# Sheet_v1.net
KiCad netlist of a schematic drawn in Altium Designer
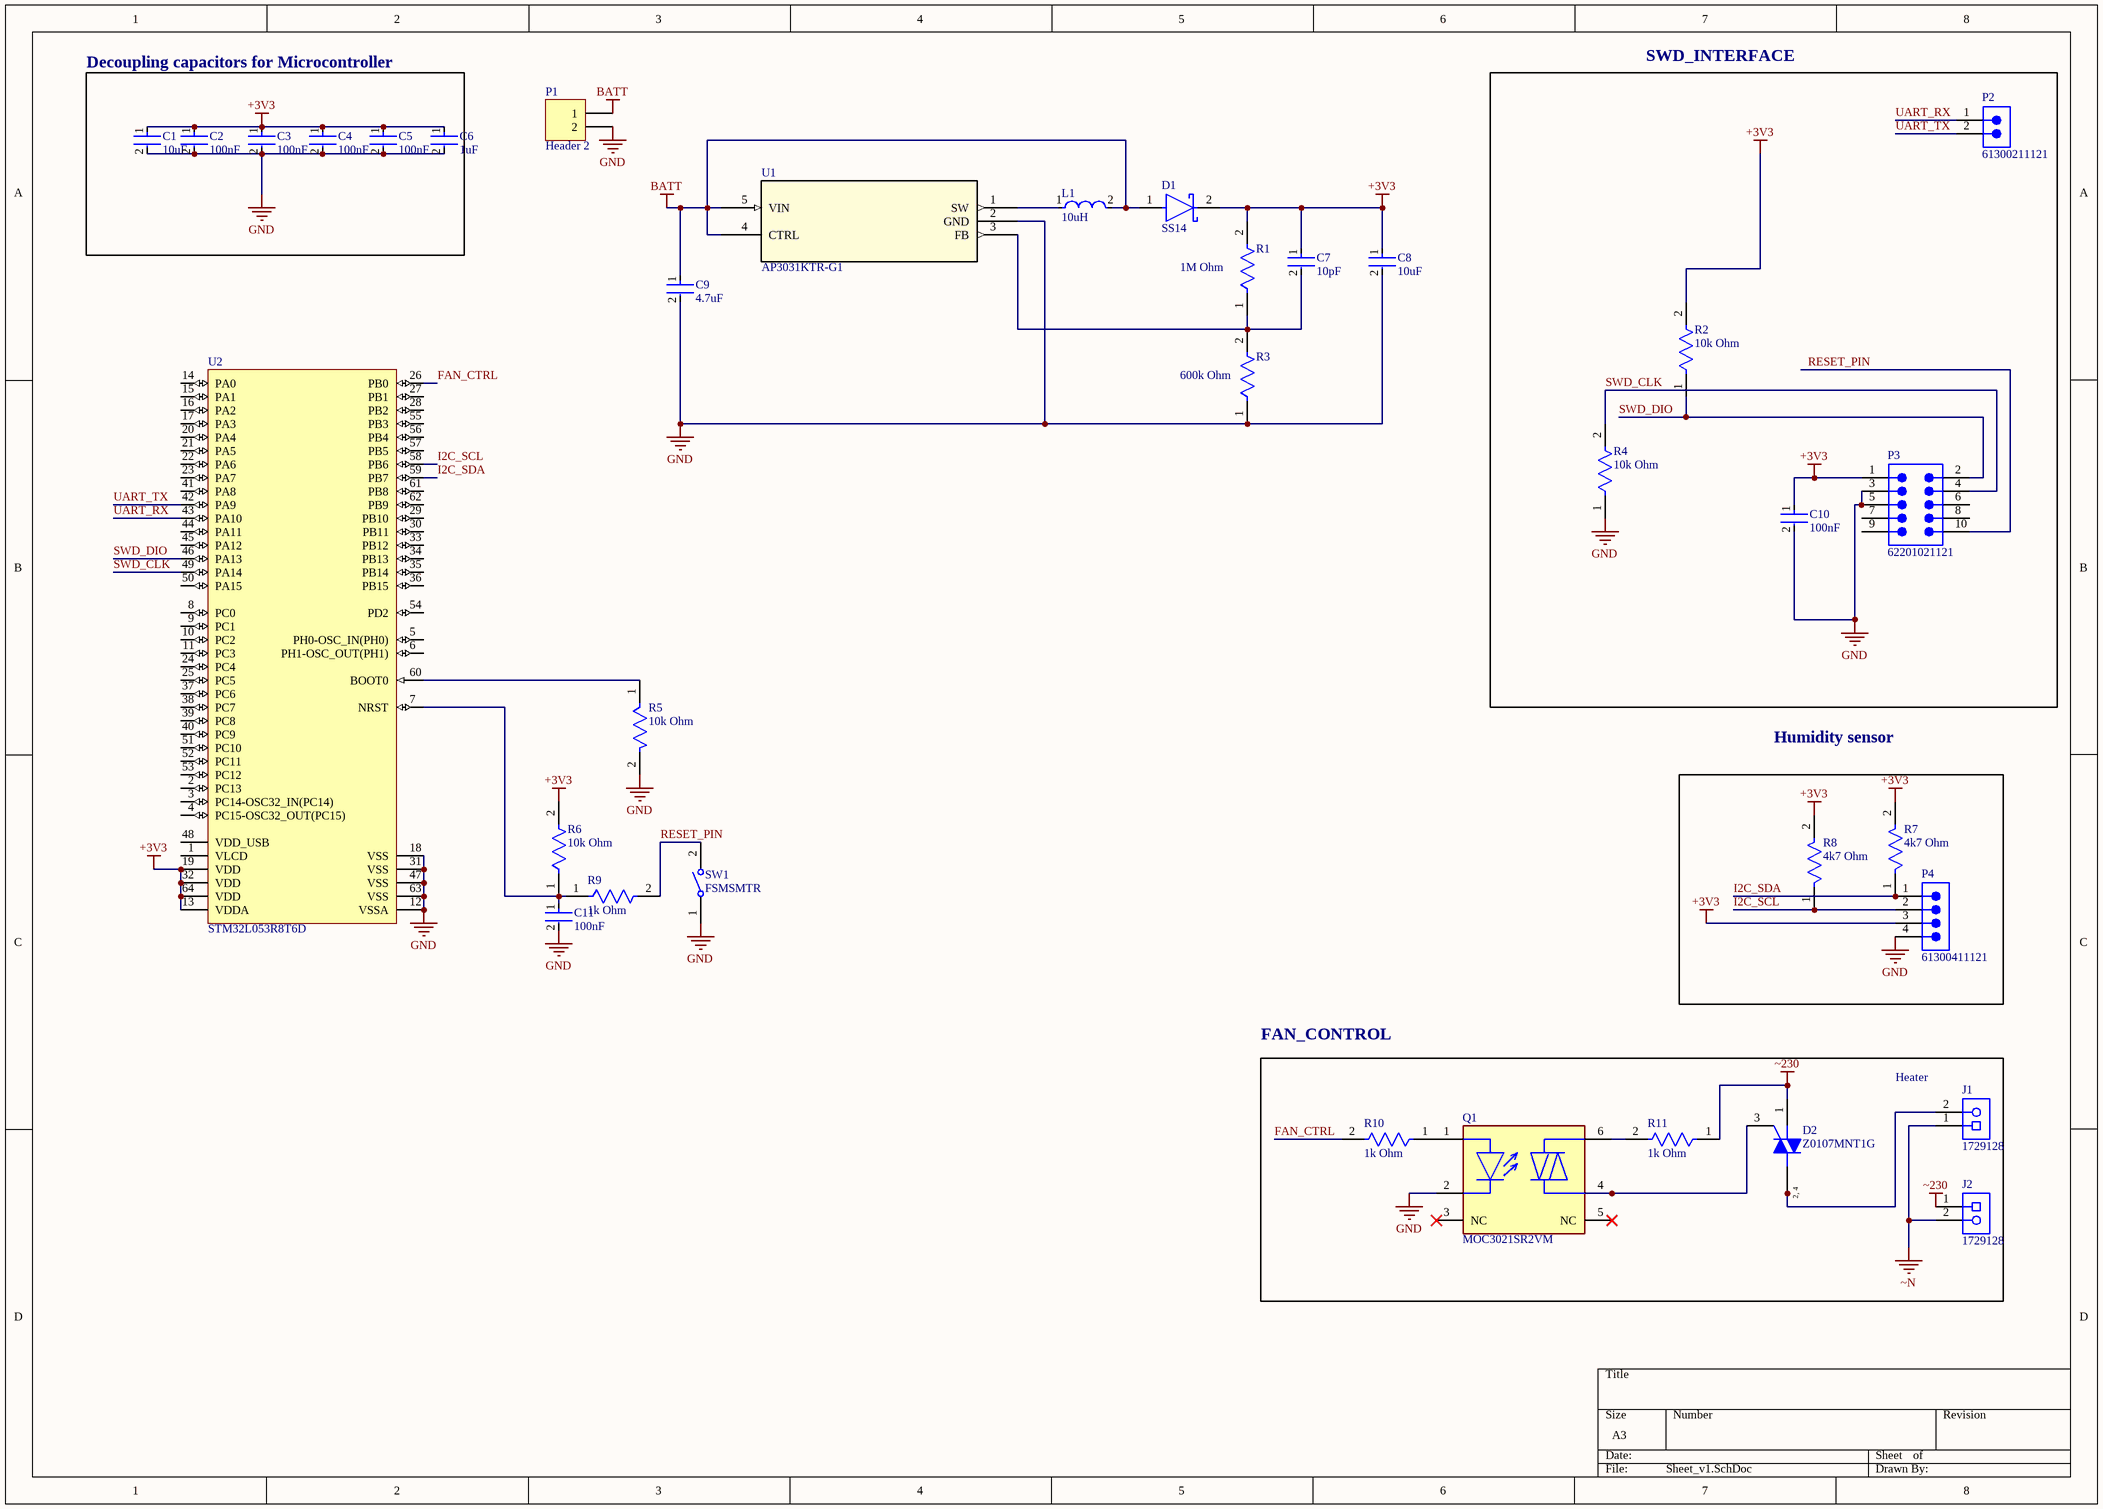
[diagram p0: Sheet_v1.SchDoc]

(export (version "E")
  (design (tool "Eeschema 10.0.6"))
  (components
    (comp (ref "C1")
      (value "10uF")
      (footprint "FP-CC0805-0_85-MFG")
      (description "CAP CER 0.1UF 50V X7R 0805")
      (fields (field (name "TOLERANCE") "0.1") (field (name "MANUFACTURER PART NUMBER") "CC0805KRX7R9BB104"))
      (libsource (lib "Altium Content Vault") (part "11868f565c42a9108669ba33697ecf6"))
    )
    (comp (ref "C2")
      (value "100nF")
      (footprint "FP-CC0805-0_85-MFG")
      (description "CAP CER 0.1UF 50V X7R 0805")
      (fields (field (name "TOLERANCE") "0.1") (field (name "MANUFACTURER PART NUMBER") "CC0805KRX7R9BB104"))
      (libsource (lib "Altium Content Vault") (part "11868f565c42a9108669ba33697ecf6"))
    )
    (comp (ref "C3")
      (value "100nF")
      (footprint "FP-CC0805-0_85-MFG")
      (description "CAP CER 0.1UF 50V X7R 0805")
      (fields (field (name "TOLERANCE") "0.1") (field (name "MANUFACTURER PART NUMBER") "CC0805KRX7R9BB104"))
      (libsource (lib "Altium Content Vault") (part "11868f565c42a9108669ba33697ecf6"))
    )
    (comp (ref "C4")
      (value "100nF")
      (footprint "FP-CC0805-0_85-MFG")
      (description "CAP CER 0.1UF 50V X7R 0805")
      (fields (field (name "TOLERANCE") "0.1") (field (name "MANUFACTURER PART NUMBER") "CC0805KRX7R9BB104"))
      (libsource (lib "Altium Content Vault") (part "11868f565c42a9108669ba33697ecf6"))
    )
    (comp (ref "C5")
      (value "100nF")
      (footprint "FP-CC0805-0_85-MFG")
      (description "CAP CER 0.1UF 50V X7R 0805")
      (fields (field (name "TOLERANCE") "0.1") (field (name "MANUFACTURER PART NUMBER") "CC0805KRX7R9BB104"))
      (libsource (lib "Altium Content Vault") (part "11868f565c42a9108669ba33697ecf6"))
    )
    (comp (ref "C6")
      (value "1uF")
      (footprint "FP-CC0805-0_85-MFG")
      (description "CAP CER 0.1UF 50V X7R 0805")
      (fields (field (name "TOLERANCE") "0.1") (field (name "MANUFACTURER PART NUMBER") "CC0805KRX7R9BB104"))
      (libsource (lib "Altium Content Vault") (part "11868f565c42a9108669ba33697ecf6"))
    )
    (comp (ref "C7")
      (value "10pF")
      (footprint "FP-CC0805-0_85-MFG")
      (description "CAP CER 0.1UF 50V X7R 0805")
      (fields (field (name "TOLERANCE") "0.1") (field (name "MANUFACTURER PART NUMBER") "CC0805KRX7R9BB104"))
      (libsource (lib "Altium Content Vault") (part "11868f565c42a9108669ba33697ecf6"))
    )
    (comp (ref "C8")
      (value "10uF")
      (footprint "FP-CC0805-0_85-MFG")
      (description "CAP CER 0.1UF 50V X7R 0805")
      (fields (field (name "TOLERANCE") "0.1") (field (name "MANUFACTURER PART NUMBER") "CC0805KRX7R9BB104"))
      (libsource (lib "Altium Content Vault") (part "11868f565c42a9108669ba33697ecf6"))
    )
    (comp (ref "C9")
      (value "4.7uF")
      (footprint "FP-CC0805-0_85-MFG")
      (description "CAP CER 0.1UF 50V X7R 0805")
      (fields (field (name "TOLERANCE") "0.1") (field (name "MANUFACTURER PART NUMBER") "CC0805KRX7R9BB104"))
      (libsource (lib "Altium Content Vault") (part "11868f565c42a9108669ba33697ecf6"))
    )
    (comp (ref "C10")
      (value "100nF")
      (footprint "FP-CC0805-0_85-MFG")
      (description "CAP CER 0.1UF 50V X7R 0805")
      (fields (field (name "TOLERANCE") "0.1") (field (name "MANUFACTURER PART NUMBER") "CC0805KRX7R9BB104"))
      (libsource (lib "Altium Content Vault") (part "11868f565c42a9108669ba33697ecf6"))
    )
    (comp (ref "C11")
      (value "100nF")
      (footprint "FP-CC0805-0_85-MFG")
      (description "CAP CER 0.1UF 50V X7R 0805")
      (fields (field (name "TOLERANCE") "0.1") (field (name "MANUFACTURER PART NUMBER") "CC0805KRX7R9BB104"))
      (libsource (lib "Altium Content Vault") (part "11868f565c42a9108669ba33697ecf6"))
    )
    (comp (ref "D1")
      (value "SS14")
      (footprint "FP-403AE-MFG")
      (description "DIODE SCHOTTKY 40V 1A SMA")
      (fields
        (field (name "MANUFACTURER") "ON Semiconductor")
        (field (name "OCTOPART") "https://octopart.com/ss14-on+semiconductor-29205033")
      )
      (libsource (lib "Altium Content Vault") (part "360ad2f4ac25a952324d13796385471"))
    )
    (comp (ref "D2")
      (value "Z0107MNT1G")
      (footprint "ONSC-SOT-223-4-318E-04_V")
      (fields (field (name "MANUFACTURER") "On Semiconductor"))
      (libsource (lib "Altium Content Vault") (part "ONSC-TRIAC-MT1MT2GMT2-4"))
    )
    (comp (ref "J1")
      (value "1729128")
      (footprint "PHOE-1729128-2_V")
      (description "PCB Terminal Block, 13.5 A, 400 V, 2-Pin THD, RoHS, Bulk")
      (fields (field (name "MANUFACTURER") "Phoenix Contact"))
      (libsource (lib "") (part "CN-2P-F-R2_1"))
    )
    (comp (ref "J2")
      (value "1729128")
      (footprint "PHOE-1729128-2_V")
      (description "PCB Terminal Block, 13.5 A, 400 V, 2-Pin THD, RoHS, Bulk")
      (fields (field (name "MANUFACTURER") "Phoenix Contact"))
      (libsource (lib "Altium Content Vault") (part "CN-2P-F-R2"))
    )
    (comp (ref "L1")
      (value "10uH")
      (footprint "FP-LQH43CN_03-MFG")
      (description "Wire Wound Ferrite Inductor for General Circuits 470μH ±10% 11.8Ω 80mA 1812")
      (fields (field (name "TOLERANCE") "10%"))
      (libsource (lib "Altium Content Vault") (part "725321dda6339637d4d059423bc1c3c"))
    )
    (comp (ref "P1")
      (value "Header 2")
      (footprint "HDR1X2")
      (description "Header, 2-Pin")
      (fields (field (name "PUBLISHER") "Altium Limited"))
      (libsource (lib "Miscellaneous Connectors") (part "Header 2"))
    )
    (comp (ref "P2")
      (value "61300211121")
      (footprint "61300211121")
      (libsource (lib "Altium Content Vault") (part "Header_Male_1R_02P"))
    )
    (comp (ref "P3")
      (value "62201021121")
      (footprint "62201021121")
      (libsource (lib "Altium Content Vault") (part "Header_Male_2R_10P"))
    )
    (comp (ref "P4")
      (value "61300411121")
      (footprint "61300411121")
      (libsource (lib "Altium Content Vault") (part "Header_Male_1R_04P"))
    )
    (comp (ref "Q1")
      (value "MOC3021SR2VM")
      (footprint "FP-646BY-MFG")
      (description "MOC3021SR2VM Triac Driver Output Optocoupler, 6-Pin DIP 400V Random Phase")
      (libsource (lib "Altium Content Vault") (part "315d33d7a3de83856d3bd334bf87c2f"))
    )
    (comp (ref "R1")
      (value "1M Ohm")
      (footprint "FP-RMCF0805-MFG")
      (description "RES 0 OHM JUMPER 1/8W 0805")
      (libsource (lib "Altium Content Vault") (part "1029c3af85768c4190bb7ad29bc67b5"))
    )
    (comp (ref "R2")
      (value "10k Ohm")
      (footprint "FP-RMCF0805-MFG")
      (description "RES 0 OHM JUMPER 1/8W 0805")
      (libsource (lib "Altium Content Vault") (part "1029c3af85768c4190bb7ad29bc67b5"))
    )
    (comp (ref "R3")
      (value "600k Ohm")
      (footprint "FP-RMCF0805-MFG")
      (description "RES 0 OHM JUMPER 1/8W 0805")
      (libsource (lib "Altium Content Vault") (part "1029c3af85768c4190bb7ad29bc67b5"))
    )
    (comp (ref "R4")
      (value "10k Ohm")
      (footprint "FP-RMCF0805-MFG")
      (description "RES 0 OHM JUMPER 1/8W 0805")
      (libsource (lib "Altium Content Vault") (part "1029c3af85768c4190bb7ad29bc67b5"))
    )
    (comp (ref "R5")
      (value "10k Ohm")
      (footprint "FP-RMCF0805-MFG")
      (description "RES 0 OHM JUMPER 1/8W 0805")
      (libsource (lib "Altium Content Vault") (part "1029c3af85768c4190bb7ad29bc67b5"))
    )
    (comp (ref "R6")
      (value "10k Ohm")
      (footprint "FP-RMCF0805-MFG")
      (description "RES 0 OHM JUMPER 1/8W 0805")
      (libsource (lib "Altium Content Vault") (part "1029c3af85768c4190bb7ad29bc67b5"))
    )
    (comp (ref "R7")
      (value "4k7 Ohm")
      (footprint "FP-RMCF0805-MFG")
      (description "RES 0 OHM JUMPER 1/8W 0805")
      (libsource (lib "Altium Content Vault") (part "1029c3af85768c4190bb7ad29bc67b5"))
    )
    (comp (ref "R8")
      (value "4k7 Ohm")
      (footprint "FP-RMCF0805-MFG")
      (description "RES 0 OHM JUMPER 1/8W 0805")
      (libsource (lib "Altium Content Vault") (part "1029c3af85768c4190bb7ad29bc67b5"))
    )
    (comp (ref "R9")
      (value "1k Ohm")
      (footprint "FP-RMCF0805-MFG")
      (description "RES 0 OHM JUMPER 1/8W 0805")
      (libsource (lib "Altium Content Vault") (part "1029c3af85768c4190bb7ad29bc67b5"))
    )
    (comp (ref "R10")
      (value "1k Ohm")
      (footprint "FP-RMCF0805-MFG")
      (description "RES 0 OHM JUMPER 1/8W 0805")
      (libsource (lib "Altium Content Vault") (part "1029c3af85768c4190bb7ad29bc67b5"))
    )
    (comp (ref "R11")
      (value "1k Ohm")
      (footprint "FP-RMCF0805-MFG")
      (description "RES 0 OHM JUMPER 1/8W 0805")
      (libsource (lib "Altium Content Vault") (part "1029c3af85768c4190bb7ad29bc67b5"))
    )
    (comp (ref "SW1")
      (value "FSMSMTR")
      (footprint "TECO-FSMSMTR_V")
      (description "FSMSM Push Button Switch, 50 mA, -35 to 85 degC, 2-Pin SMD, RoHS, Tape and Reel")
      (fields (field (name "MANUFACTURER") "TE Connectivity"))
      (libsource (lib "Altium Content Vault") (part "SW-SPST-2_C"))
    )
    (comp (ref "U1")
      (value "AP3031KTR-G1")
      (footprint "SOT23-6_DIO")
      (description "No Description Available")
      (libsource (lib "AP3031KTR-G1") (part "AP3031KTR-G1"))
    )
    (comp (ref "U2")
      (value "STM32L053R8T6D")
      (footprint "STM-LQFP64_L")
      (libsource (lib "Altium Content Vault") (part "MC-ARM-STM32L053-LQFP64"))
    )
  )
  (nets
    (net (code "1") (name "+3V3") (class "Default")
      (node (ref "C1") (pin "1") (pinfunction "1_1") (pintype "passive"))
      (node (ref "C10") (pin "1") (pinfunction "1_1") (pintype "passive"))
      (node (ref "C2") (pin "1") (pinfunction "1_1") (pintype "passive"))
      (node (ref "C3") (pin "1") (pinfunction "1_1") (pintype "passive"))
      (node (ref "C4") (pin "1") (pinfunction "1_1") (pintype "passive"))
      (node (ref "C5") (pin "1") (pinfunction "1_1") (pintype "passive"))
      (node (ref "C6") (pin "1") (pinfunction "1_1") (pintype "passive"))
      (node (ref "C7") (pin "1") (pinfunction "1_1") (pintype "passive"))
      (node (ref "C8") (pin "1") (pinfunction "1_1") (pintype "passive"))
      (node (ref "D1") (pin "2") (pinfunction "C_2") (pintype "passive"))
      (node (ref "P3") (pin "1") (pinfunction "1_1") (pintype "passive"))
      (node (ref "P4") (pin "3") (pinfunction "3_3") (pintype "passive"))
      (node (ref "R1") (pin "2") (pinfunction "2_2") (pintype "passive"))
      (node (ref "R2") (pin "2") (pinfunction "2_2") (pintype "passive"))
      (node (ref "R6") (pin "2") (pinfunction "2_2") (pintype "passive"))
      (node (ref "R7") (pin "2") (pinfunction "2_2") (pintype "passive"))
      (node (ref "R8") (pin "2") (pinfunction "2_2") (pintype "passive"))
      (node (ref "U2") (pin "13") (pinfunction "VDDA_13") (pintype "power_in"))
      (node (ref "U2") (pin "19") (pinfunction "VDD_19") (pintype "power_in"))
      (node (ref "U2") (pin "32") (pinfunction "VDD_32") (pintype "power_in"))
      (node (ref "U2") (pin "64") (pinfunction "VDD_64") (pintype "power_in"))
    )
    (net (code "2") (name "/FAN_CTRL") (class "Default")
      (node (ref "R10") (pin "2") (pinfunction "2_2") (pintype "passive"))
      (node (ref "U2") (pin "26") (pinfunction "PB0_26") (pintype "bidirectional"))
    )
    (net (code "3") (name "/I2C_SCL") (class "Default")
      (node (ref "P4") (pin "2") (pinfunction "2_2") (pintype "passive"))
      (node (ref "R8") (pin "1") (pinfunction "1_1") (pintype "passive"))
      (node (ref "U2") (pin "58") (pinfunction "PB6_58") (pintype "bidirectional"))
    )
    (net (code "4") (name "/I2C_SDA") (class "Default")
      (node (ref "P4") (pin "1") (pinfunction "1_1") (pintype "passive"))
      (node (ref "R7") (pin "1") (pinfunction "1_1") (pintype "passive"))
      (node (ref "U2") (pin "59") (pinfunction "PB7_59") (pintype "bidirectional"))
    )
    (net (code "5") (name "/RESET_PIN") (class "Default")
      (node (ref "P3") (pin "10") (pinfunction "10_10") (pintype "passive"))
      (node (ref "R9") (pin "2") (pinfunction "2_2") (pintype "passive"))
      (node (ref "SW1") (pin "2") (pinfunction "2_2") (pintype "passive"))
    )
    (net (code "6") (name "/SWD_CLK") (class "Default")
      (node (ref "P3") (pin "4") (pinfunction "4_4") (pintype "passive"))
      (node (ref "R4") (pin "2") (pinfunction "2_2") (pintype "passive"))
      (node (ref "U2") (pin "49") (pinfunction "PA14_49") (pintype "bidirectional"))
    )
    (net (code "7") (name "/SWD_DIO") (class "Default")
      (node (ref "P3") (pin "2") (pinfunction "2_2") (pintype "passive"))
      (node (ref "R2") (pin "1") (pinfunction "1_1") (pintype "passive"))
      (node (ref "U2") (pin "46") (pinfunction "PA13_46") (pintype "bidirectional"))
    )
    (net (code "8") (name "/UART_RX") (class "Default")
      (node (ref "P2") (pin "1") (pinfunction "1_1") (pintype "passive"))
      (node (ref "U2") (pin "43") (pinfunction "PA10_43") (pintype "bidirectional"))
    )
    (net (code "9") (name "/UART_TX") (class "Default")
      (node (ref "P2") (pin "2") (pinfunction "2_2") (pintype "passive"))
      (node (ref "U2") (pin "42") (pinfunction "PA9_42") (pintype "bidirectional"))
    )
    (net (code "10") (name "BATT") (class "Default")
      (node (ref "C9") (pin "1") (pinfunction "1_1") (pintype "passive"))
      (node (ref "D1") (pin "1") (pinfunction "A_1") (pintype "passive"))
      (node (ref "L1") (pin "2") (pinfunction "2_2") (pintype "passive"))
      (node (ref "P1") (pin "1") (pinfunction "1_1") (pintype "passive"))
      (node (ref "U1") (pin "4") (pinfunction "CTRL_4") (pintype "passive"))
      (node (ref "U1") (pin "5") (pinfunction "VIN_5") (pintype "input"))
    )
    (net (code "11") (name "GND") (class "Default")
      (node (ref "C1") (pin "2") (pinfunction "2_2") (pintype "passive"))
      (node (ref "C10") (pin "2") (pinfunction "2_2") (pintype "passive"))
      (node (ref "C11") (pin "2") (pinfunction "2_2") (pintype "passive"))
      (node (ref "C2") (pin "2") (pinfunction "2_2") (pintype "passive"))
      (node (ref "C3") (pin "2") (pinfunction "2_2") (pintype "passive"))
      (node (ref "C4") (pin "2") (pinfunction "2_2") (pintype "passive"))
      (node (ref "C5") (pin "2") (pinfunction "2_2") (pintype "passive"))
      (node (ref "C6") (pin "2") (pinfunction "2_2") (pintype "passive"))
      (node (ref "C8") (pin "2") (pinfunction "2_2") (pintype "passive"))
      (node (ref "C9") (pin "2") (pinfunction "2_2") (pintype "passive"))
      (node (ref "P1") (pin "2") (pinfunction "2_2") (pintype "passive"))
      (node (ref "P3") (pin "3") (pinfunction "3_3") (pintype "passive"))
      (node (ref "P3") (pin "5") (pinfunction "5_5") (pintype "passive"))
      (node (ref "P4") (pin "4") (pinfunction "4_4") (pintype "passive"))
      (node (ref "Q1") (pin "2") (pinfunction "C_2") (pintype "passive"))
      (node (ref "R3") (pin "1") (pinfunction "1_1") (pintype "passive"))
      (node (ref "R4") (pin "1") (pinfunction "1_1") (pintype "passive"))
      (node (ref "R5") (pin "2") (pinfunction "2_2") (pintype "passive"))
      (node (ref "SW1") (pin "1") (pinfunction "1_1") (pintype "passive"))
      (node (ref "U1") (pin "2") (pinfunction "GND_2") (pintype "power_in"))
      (node (ref "U2") (pin "12") (pinfunction "VSSA_12") (pintype "power_in"))
      (node (ref "U2") (pin "18") (pinfunction "VSS_18") (pintype "power_in"))
      (node (ref "U2") (pin "31") (pinfunction "VSS_31") (pintype "power_in"))
      (node (ref "U2") (pin "47") (pinfunction "VSS_47") (pintype "power_in"))
      (node (ref "U2") (pin "63") (pinfunction "VSS_63") (pintype "power_in"))
    )
    (net (code "12") (name "Net-(D2-G)") (class "Default")
      (node (ref "D2") (pin "3") (pinfunction "G_3") (pintype "passive"))
      (node (ref "Q1") (pin "4") (pinfunction "1_MAIN_TERM_4") (pintype "passive"))
    )
    (net (code "13") (name "Net-(D2-MT2-Pad2)") (class "Default")
      (node (ref "D2") (pin "2") (pinfunction "MT2_2") (pintype "passive"))
      (node (ref "D2") (pin "4") (pinfunction "MT2_4") (pintype "passive"))
      (node (ref "J1") (pin "2") (pinfunction "2_2") (pintype "passive"))
    )
    (net (code "14") (name "Net-(Q1-2_MAIN_TERM)") (class "Default")
      (node (ref "Q1") (pin "6") (pinfunction "2_MAIN_TERM_6") (pintype "passive"))
      (node (ref "R11") (pin "2") (pinfunction "2_2") (pintype "passive"))
    )
    (net (code "15") (name "Net-(Q1-A)") (class "Default")
      (node (ref "Q1") (pin "1") (pinfunction "A_1") (pintype "passive"))
      (node (ref "R10") (pin "1") (pinfunction "1_1") (pintype "passive"))
    )
    (net (code "16") (name "Net-(U1-FB)") (class "Default")
      (node (ref "C7") (pin "2") (pinfunction "2_2") (pintype "passive"))
      (node (ref "R1") (pin "1") (pinfunction "1_1") (pintype "passive"))
      (node (ref "R3") (pin "2") (pinfunction "2_2") (pintype "passive"))
      (node (ref "U1") (pin "3") (pinfunction "FB_3") (pintype "output"))
    )
    (net (code "17") (name "Net-(U1-SW)") (class "Default")
      (node (ref "L1") (pin "1") (pinfunction "1_1") (pintype "passive"))
      (node (ref "U1") (pin "1") (pinfunction "SW_1") (pintype "output"))
    )
    (net (code "18") (name "Net-(U2-BOOT0)") (class "Default")
      (node (ref "R5") (pin "1") (pinfunction "1_1") (pintype "passive"))
      (node (ref "U2") (pin "60") (pinfunction "BOOT0_60") (pintype "input"))
    )
    (net (code "19") (name "Net-(U2-NRST)") (class "Default")
      (node (ref "C11") (pin "1") (pinfunction "1_1") (pintype "passive"))
      (node (ref "R6") (pin "1") (pinfunction "1_1") (pintype "passive"))
      (node (ref "R9") (pin "1") (pinfunction "1_1") (pintype "passive"))
      (node (ref "U2") (pin "7") (pinfunction "NRST_7") (pintype "bidirectional"))
    )
    (net (code "20") (name "unconnected-(P3-Pad6)") (class "Default")
      (node (ref "P3") (pin "6") (pinfunction "6_6") (pintype "passive"))
    )
    (net (code "21") (name "unconnected-(P3-Pad7)") (class "Default")
      (node (ref "P3") (pin "7") (pinfunction "7_7") (pintype "passive"))
    )
    (net (code "22") (name "unconnected-(P3-Pad8)") (class "Default")
      (node (ref "P3") (pin "8") (pinfunction "8_8") (pintype "passive"))
    )
    (net (code "23") (name "unconnected-(P3-Pad9)") (class "Default")
      (node (ref "P3") (pin "9") (pinfunction "9_9") (pintype "passive"))
    )
    (net (code "24") (name "unconnected-(Q1-NC-Pad3)") (class "Default")
      (node (ref "Q1") (pin "3") (pinfunction "NC_3") (pintype "passive+no_connect"))
    )
    (net (code "25") (name "unconnected-(Q1-NC-Pad5)") (class "Default")
      (node (ref "Q1") (pin "5") (pinfunction "NC_5") (pintype "passive+no_connect"))
    )
    (net (code "26") (name "unconnected-(U2-PA0-Pad14)") (class "Default")
      (node (ref "U2") (pin "14") (pinfunction "PA0_14") (pintype "bidirectional"))
    )
    (net (code "27") (name "unconnected-(U2-PA1-Pad15)") (class "Default")
      (node (ref "U2") (pin "15") (pinfunction "PA1_15") (pintype "bidirectional"))
    )
    (net (code "28") (name "unconnected-(U2-PA2-Pad16)") (class "Default")
      (node (ref "U2") (pin "16") (pinfunction "PA2_16") (pintype "bidirectional"))
    )
    (net (code "29") (name "unconnected-(U2-PA3-Pad17)") (class "Default")
      (node (ref "U2") (pin "17") (pinfunction "PA3_17") (pintype "bidirectional"))
    )
    (net (code "30") (name "unconnected-(U2-PA4-Pad20)") (class "Default")
      (node (ref "U2") (pin "20") (pinfunction "PA4_20") (pintype "bidirectional"))
    )
    (net (code "31") (name "unconnected-(U2-PA5-Pad21)") (class "Default")
      (node (ref "U2") (pin "21") (pinfunction "PA5_21") (pintype "bidirectional"))
    )
    (net (code "32") (name "unconnected-(U2-PA6-Pad22)") (class "Default")
      (node (ref "U2") (pin "22") (pinfunction "PA6_22") (pintype "bidirectional"))
    )
    (net (code "33") (name "unconnected-(U2-PA7-Pad23)") (class "Default")
      (node (ref "U2") (pin "23") (pinfunction "PA7_23") (pintype "bidirectional"))
    )
    (net (code "34") (name "unconnected-(U2-PA8-Pad41)") (class "Default")
      (node (ref "U2") (pin "41") (pinfunction "PA8_41") (pintype "bidirectional"))
    )
    (net (code "35") (name "unconnected-(U2-PA11-Pad44)") (class "Default")
      (node (ref "U2") (pin "44") (pinfunction "PA11_44") (pintype "bidirectional"))
    )
    (net (code "36") (name "unconnected-(U2-PA12-Pad45)") (class "Default")
      (node (ref "U2") (pin "45") (pinfunction "PA12_45") (pintype "bidirectional"))
    )
    (net (code "37") (name "unconnected-(U2-PA15-Pad50)") (class "Default")
      (node (ref "U2") (pin "50") (pinfunction "PA15_50") (pintype "bidirectional"))
    )
    (net (code "38") (name "unconnected-(U2-PB1-Pad27)") (class "Default")
      (node (ref "U2") (pin "27") (pinfunction "PB1_27") (pintype "bidirectional"))
    )
    (net (code "39") (name "unconnected-(U2-PB2-Pad28)") (class "Default")
      (node (ref "U2") (pin "28") (pinfunction "PB2_28") (pintype "bidirectional"))
    )
    (net (code "40") (name "unconnected-(U2-PB3-Pad55)") (class "Default")
      (node (ref "U2") (pin "55") (pinfunction "PB3_55") (pintype "bidirectional"))
    )
    (net (code "41") (name "unconnected-(U2-PB4-Pad56)") (class "Default")
      (node (ref "U2") (pin "56") (pinfunction "PB4_56") (pintype "bidirectional"))
    )
    (net (code "42") (name "unconnected-(U2-PB5-Pad57)") (class "Default")
      (node (ref "U2") (pin "57") (pinfunction "PB5_57") (pintype "bidirectional"))
    )
    (net (code "43") (name "unconnected-(U2-PB8-Pad61)") (class "Default")
      (node (ref "U2") (pin "61") (pinfunction "PB8_61") (pintype "bidirectional"))
    )
    (net (code "44") (name "unconnected-(U2-PB9-Pad62)") (class "Default")
      (node (ref "U2") (pin "62") (pinfunction "PB9_62") (pintype "bidirectional"))
    )
    (net (code "45") (name "unconnected-(U2-PB10-Pad29)") (class "Default")
      (node (ref "U2") (pin "29") (pinfunction "PB10_29") (pintype "bidirectional"))
    )
    (net (code "46") (name "unconnected-(U2-PB11-Pad30)") (class "Default")
      (node (ref "U2") (pin "30") (pinfunction "PB11_30") (pintype "bidirectional"))
    )
    (net (code "47") (name "unconnected-(U2-PB12-Pad33)") (class "Default")
      (node (ref "U2") (pin "33") (pinfunction "PB12_33") (pintype "bidirectional"))
    )
    (net (code "48") (name "unconnected-(U2-PB13-Pad34)") (class "Default")
      (node (ref "U2") (pin "34") (pinfunction "PB13_34") (pintype "bidirectional"))
    )
    (net (code "49") (name "unconnected-(U2-PB14-Pad35)") (class "Default")
      (node (ref "U2") (pin "35") (pinfunction "PB14_35") (pintype "bidirectional"))
    )
    (net (code "50") (name "unconnected-(U2-PB15-Pad36)") (class "Default")
      (node (ref "U2") (pin "36") (pinfunction "PB15_36") (pintype "bidirectional"))
    )
    (net (code "51") (name "unconnected-(U2-PC0-Pad8)") (class "Default")
      (node (ref "U2") (pin "8") (pinfunction "PC0_8") (pintype "bidirectional"))
    )
    (net (code "52") (name "unconnected-(U2-PC1-Pad9)") (class "Default")
      (node (ref "U2") (pin "9") (pinfunction "PC1_9") (pintype "bidirectional"))
    )
    (net (code "53") (name "unconnected-(U2-PC2-Pad10)") (class "Default")
      (node (ref "U2") (pin "10") (pinfunction "PC2_10") (pintype "bidirectional"))
    )
    (net (code "54") (name "unconnected-(U2-PC3-Pad11)") (class "Default")
      (node (ref "U2") (pin "11") (pinfunction "PC3_11") (pintype "bidirectional"))
    )
    (net (code "55") (name "unconnected-(U2-PC4-Pad24)") (class "Default")
      (node (ref "U2") (pin "24") (pinfunction "PC4_24") (pintype "bidirectional"))
    )
    (net (code "56") (name "unconnected-(U2-PC5-Pad25)") (class "Default")
      (node (ref "U2") (pin "25") (pinfunction "PC5_25") (pintype "bidirectional"))
    )
    (net (code "57") (name "unconnected-(U2-PC6-Pad37)") (class "Default")
      (node (ref "U2") (pin "37") (pinfunction "PC6_37") (pintype "bidirectional"))
    )
    (net (code "58") (name "unconnected-(U2-PC7-Pad38)") (class "Default")
      (node (ref "U2") (pin "38") (pinfunction "PC7_38") (pintype "bidirectional"))
    )
    (net (code "59") (name "unconnected-(U2-PC8-Pad39)") (class "Default")
      (node (ref "U2") (pin "39") (pinfunction "PC8_39") (pintype "bidirectional"))
    )
    (net (code "60") (name "unconnected-(U2-PC9-Pad40)") (class "Default")
      (node (ref "U2") (pin "40") (pinfunction "PC9_40") (pintype "bidirectional"))
    )
    (net (code "61") (name "unconnected-(U2-PC10-Pad51)") (class "Default")
      (node (ref "U2") (pin "51") (pinfunction "PC10_51") (pintype "bidirectional"))
    )
    (net (code "62") (name "unconnected-(U2-PC11-Pad52)") (class "Default")
      (node (ref "U2") (pin "52") (pinfunction "PC11_52") (pintype "bidirectional"))
    )
    (net (code "63") (name "unconnected-(U2-PC12-Pad53)") (class "Default")
      (node (ref "U2") (pin "53") (pinfunction "PC12_53") (pintype "bidirectional"))
    )
    (net (code "64") (name "unconnected-(U2-PC13-Pad2)") (class "Default")
      (node (ref "U2") (pin "2") (pinfunction "PC13_2") (pintype "bidirectional"))
    )
    (net (code "65") (name "unconnected-(U2-PC14-OSC32_IN(PC14)-Pad3)") (class "Default")
      (node (ref "U2") (pin "3") (pinfunction "PC14-OSC32_IN(PC14)_3") (pintype "bidirectional"))
    )
    (net (code "66") (name "unconnected-(U2-PC15-OSC32_OUT(PC15)-Pad4)") (class "Default")
      (node (ref "U2") (pin "4") (pinfunction "PC15-OSC32_OUT(PC15)_4") (pintype "bidirectional"))
    )
    (net (code "67") (name "unconnected-(U2-PD2-Pad54)") (class "Default")
      (node (ref "U2") (pin "54") (pinfunction "PD2_54") (pintype "bidirectional"))
    )
    (net (code "68") (name "unconnected-(U2-PH0-OSC_IN(PH0)-Pad5)") (class "Default")
      (node (ref "U2") (pin "5") (pinfunction "PH0-OSC_IN(PH0)_5") (pintype "bidirectional"))
    )
    (net (code "69") (name "unconnected-(U2-PH1-OSC_OUT(PH1)-Pad6)") (class "Default")
      (node (ref "U2") (pin "6") (pinfunction "PH1-OSC_OUT(PH1)_6") (pintype "bidirectional"))
    )
    (net (code "70") (name "unconnected-(U2-VDD_USB-Pad48)") (class "Default")
      (node (ref "U2") (pin "48") (pinfunction "VDD_USB_48") (pintype "power_in"))
    )
    (net (code "71") (name "unconnected-(U2-VLCD-Pad1)") (class "Default")
      (node (ref "U2") (pin "1") (pinfunction "VLCD_1") (pintype "power_in"))
    )
    (net (code "72") (name "~230") (class "Default")
      (node (ref "D2") (pin "1") (pinfunction "MT1_1") (pintype "passive"))
      (node (ref "J2") (pin "1") (pinfunction "1_1") (pintype "passive"))
      (node (ref "R11") (pin "1") (pinfunction "1_1") (pintype "passive"))
    )
    (net (code "73") (name "~N") (class "Default")
      (node (ref "J1") (pin "1") (pinfunction "1_1") (pintype "passive"))
      (node (ref "J2") (pin "2") (pinfunction "2_2") (pintype "passive"))
    )
  )
)
